# CATS-FAT-MCU.net
KiCad netlist of a schematic drawn in Altium Designer
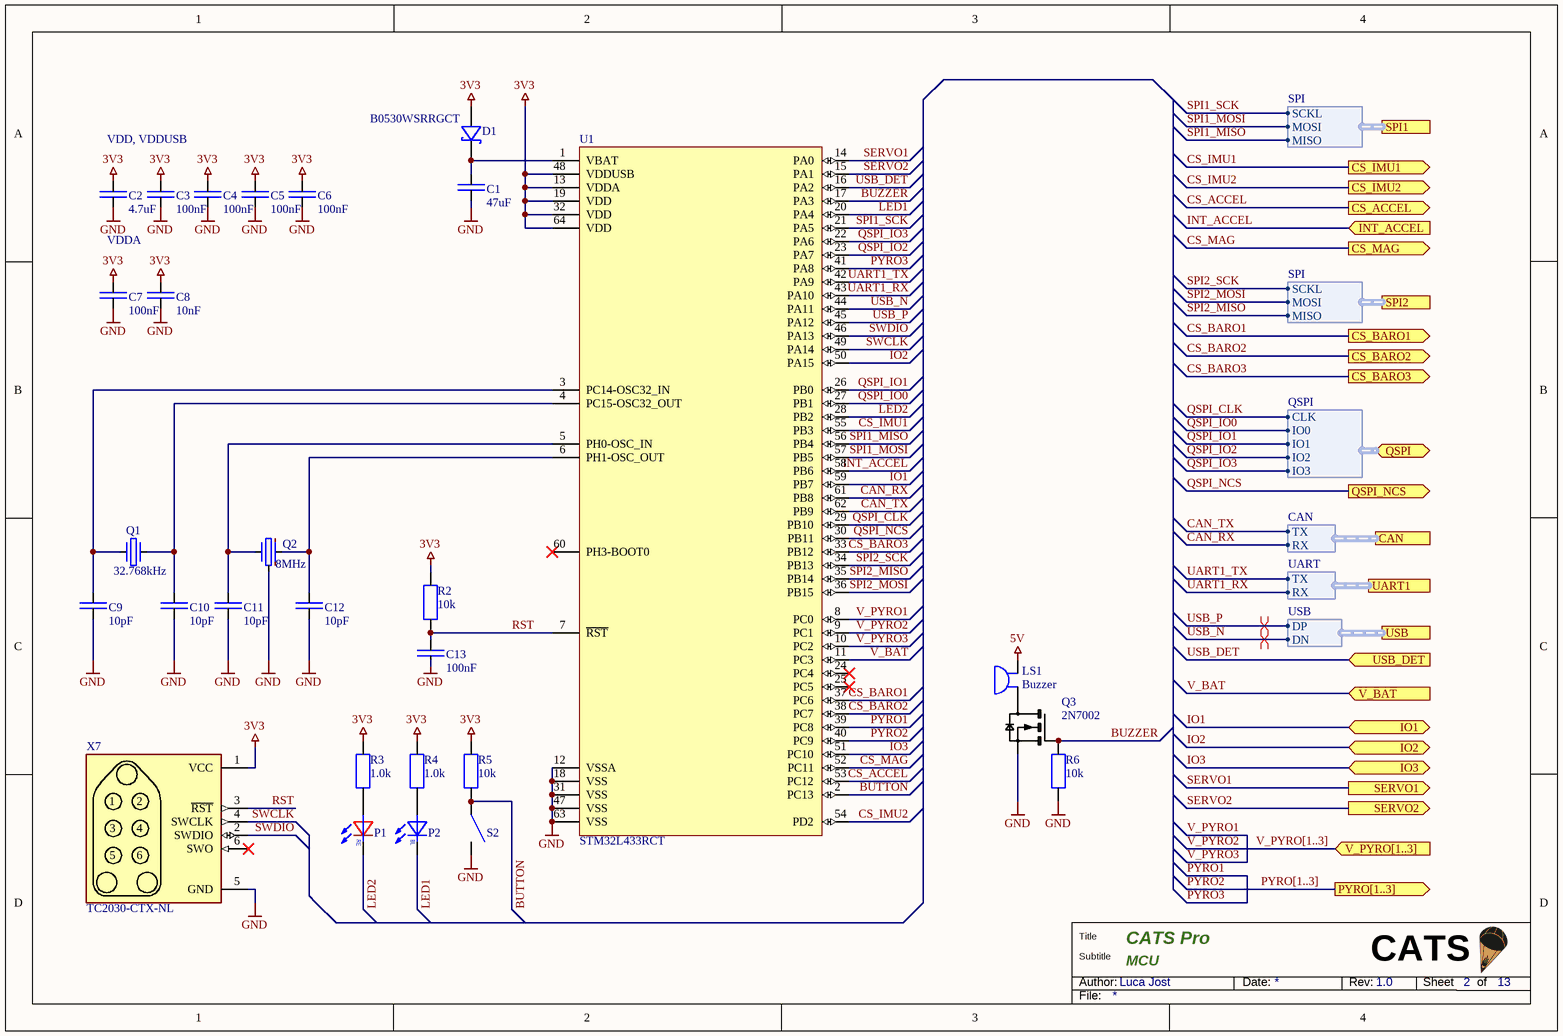
[diagram p0: CATS-FAT-MCU.SchDoc]

(export (version "E")
  (design (tool "Eeschema 10.0.6"))
  (components
    (comp (ref "C1")
      (value "47uF")
      (footprint "SMD Keramikkondensator 0805")
      (description "SMD Ceramic Capacitor E6")
      (libsource (lib "Ceramic Capacitors-E6") (part "E6 - 47uF"))
    )
    (comp (ref "C2")
      (value "4.7uF")
      (footprint "SMD Keramikkondensator 0603")
      (description "SMD Ceramic Capacitor E6")
      (libsource (lib "Ceramic Capacitors-E6") (part "E6 - 4.7uF"))
    )
    (comp (ref "C3")
      (value "100nF")
      (footprint "SMD Keramikkondensator 0603")
      (description "SMD Ceramic Capacitor E6")
      (libsource (lib "Ceramic Capacitors-E6") (part "E6 - 100nF"))
    )
    (comp (ref "C4")
      (value "100nF")
      (footprint "SMD Keramikkondensator 0603")
      (description "SMD Ceramic Capacitor E6")
      (libsource (lib "Ceramic Capacitors-E6") (part "E6 - 100nF"))
    )
    (comp (ref "C5")
      (value "100nF")
      (footprint "SMD Keramikkondensator 0603")
      (description "SMD Ceramic Capacitor E6")
      (libsource (lib "Ceramic Capacitors-E6") (part "E6 - 100nF"))
    )
    (comp (ref "C6")
      (value "100nF")
      (footprint "SMD Keramikkondensator 0603")
      (description "SMD Ceramic Capacitor E6")
      (libsource (lib "Ceramic Capacitors-E6") (part "E6 - 100nF"))
    )
    (comp (ref "C7")
      (value "100nF")
      (footprint "SMD Keramikkondensator 0603")
      (description "SMD Ceramic Capacitor E6")
      (libsource (lib "Ceramic Capacitors-E6") (part "E6 - 100nF"))
    )
    (comp (ref "C8")
      (value "10nF")
      (footprint "SMD Keramikkondensator 0603")
      (description "SMD Ceramic Capacitor E6")
      (libsource (lib "Ceramic Capacitors-E6") (part "E6 - 10nF"))
    )
    (comp (ref "C9")
      (value "10pF")
      (footprint "SMD Keramikkondensator 0603")
      (description "SMD Ceramic Capacitor E6")
      (libsource (lib "Ceramic Capacitors-E6") (part "E6 - 10pF"))
    )
    (comp (ref "C10")
      (value "10pF")
      (footprint "SMD Keramikkondensator 0603")
      (description "SMD Ceramic Capacitor E6")
      (libsource (lib "Ceramic Capacitors-E6") (part "E6 - 10pF"))
    )
    (comp (ref "C11")
      (value "10pF")
      (footprint "SMD Keramikkondensator 0603")
      (description "SMD Ceramic Capacitor E6")
      (libsource (lib "Ceramic Capacitors-E6") (part "E6 - 10pF"))
    )
    (comp (ref "C12")
      (value "10pF")
      (footprint "SMD Keramikkondensator 0603")
      (description "SMD Ceramic Capacitor E6")
      (libsource (lib "Ceramic Capacitors-E6") (part "E6 - 10pF"))
    )
    (comp (ref "C13")
      (value "100nF")
      (footprint "SMD Keramikkondensator 0603")
      (description "SMD Ceramic Capacitor E6")
      (libsource (lib "Ceramic Capacitors-E6") (part "E6 - 100nF"))
    )
    (comp (ref "D1")
      (value "B0530WSRRGCT")
      (footprint "SMD Diode SOD-323F")
      (description "200mW, 0.47V Schottky Barrier Diode")
      (libsource (lib "Diodes") (part "B0530WSRRGCT"))
    )
    (comp (ref "LS1")
      (value "Buzzer")
      (footprint "SMD BUZZER CMT-8504")
      (description "Buzzers Indicator, Internally Driven Piezo 12V 10mA 3kHz 100dB @ 12V, 10cm Through Hole PC Pins")
      (libsource (lib "Other") (part "Buzzer"))
    )
    (comp (ref "P1")
      (value "LED")
      (footprint "SMD LED 0603")
      (description "Color LED")
      (libsource (lib "") (part "LED_1"))
    )
    (comp (ref "P2")
      (value "LED")
      (footprint "SMD LED 0603")
      (description "Color LED")
      (libsource (lib "Diodes") (part "LED"))
    )
    (comp (ref "Q1")
      (value "32.768kHz")
      (footprint "SMD Crystal 3.2x1.5x0.9")
      (description "CRYSTAL 32.7680KHZ 9PF SMD")
      (libsource (lib "Other") (part "Crystal 32.768kHz"))
    )
    (comp (ref "Q2")
      (value "8MHz")
      (footprint "SMD Crystal 3.2X2.5X0.8")
      (description "SMD Crystal Resonators 8MHz ±10ppm SMD,3.2x2.5mm")
      (libsource (lib "Other") (part "Crystal"))
    )
    (comp (ref "Q3")
      (value "2N7002")
      (footprint "SMD MOSFET SOT-23")
      (description "MOSFET N-Channel 20V / 115mA")
      (libsource (lib "Electronic Switches") (part "2N7002"))
    )
    (comp (ref "R2")
      (value "10k")
      (footprint "SMD Widerstand 0603")
      (description "SMD Chip Resistor E24")
      (libsource (lib "Resistors-E24") (part "E24 - 10k"))
    )
    (comp (ref "R3")
      (value "1.0k")
      (footprint "SMD Widerstand 0603")
      (description "SMD Chip Resistor E24")
      (libsource (lib "Resistors-E24") (part "E24 - 1.0k"))
    )
    (comp (ref "R4")
      (value "1.0k")
      (footprint "SMD Widerstand 0603")
      (description "SMD Chip Resistor E24")
      (libsource (lib "Resistors-E24") (part "E24 - 1.0k"))
    )
    (comp (ref "R5")
      (value "10k")
      (footprint "SMD Widerstand 0603")
      (description "SMD Chip Resistor E24")
      (libsource (lib "Resistors-E24") (part "E24 - 10k"))
    )
    (comp (ref "R6")
      (value "10k")
      (footprint "SMD Widerstand 0603")
      (description "SMD Chip Resistor E24")
      (libsource (lib "Resistors-E24") (part "E24 - 10k"))
    )
    (comp (ref "S2")
      (value "SMD-Button")
      (footprint "SMD Button 2.5x3x1.2")
      (description "Button SPST")
      (libsource (lib "Switches") (part "Button 3mmx2.5mm"))
    )
    (comp (ref "U1")
      (value "STM32L433RCT")
      (footprint "SMD IC LQFP64-N")
      (description "ARM® Cortex®-M4 series Microcontroller IC 32-Bit 80MHz 256KB (256K x 8) FLASH 64-LQFP (10x10)")
      (libsource (lib "Microcontrollers") (part "STM32L433RCT"))
    )
    (comp (ref "X7")
      (value "TC2030-CTX-NL")
      (footprint "SMD Connector TC2030 w/ holes")
      (description "Tag-Connect for ARM-Cortex (6-Pin)")
      (libsource (lib "Connectors") (part "TC2030-CTX-NL"))
    )
  )
  (nets
    (net (code "6") (name "/BUTTON") (class "Default")
      (node (ref "R5") (pin "1") (pinfunction "1_1") (pintype "passive"))
      (node (ref "S2") (pin "1") (pinfunction "1_1") (pintype "passive"))
      (node (ref "U1") (pin "2") (pinfunction "PC13_2") (pintype "bidirectional"))
    )
    (net (code "7") (name "/BUZZER") (class "Default")
      (node (ref "Q3") (pin "G") (pinfunction "G_G") (pintype "passive"))
      (node (ref "R6") (pin "2") (pinfunction "2_2") (pintype "passive"))
      (node (ref "U1") (pin "17") (pinfunction "PA3_17") (pintype "bidirectional"))
    )
    (net (code "8") (name "/CAN_RX") (class "Default")
      (node (ref "U1") (pin "61") (pinfunction "PB8_61") (pintype "bidirectional"))
    )
    (net (code "9") (name "/CAN_TX") (class "Default")
      (node (ref "U1") (pin "62") (pinfunction "PB9_62") (pintype "bidirectional"))
    )
    (net (code "10") (name "/CS_ACCEL") (class "Default")
      (node (ref "U1") (pin "53") (pinfunction "PC12_53") (pintype "bidirectional"))
    )
    (net (code "11") (name "/CS_BARO1") (class "Default")
      (node (ref "U1") (pin "37") (pinfunction "PC6_37") (pintype "bidirectional"))
    )
    (net (code "12") (name "/CS_BARO2") (class "Default")
      (node (ref "U1") (pin "38") (pinfunction "PC7_38") (pintype "bidirectional"))
    )
    (net (code "13") (name "/CS_BARO3") (class "Default")
      (node (ref "U1") (pin "33") (pinfunction "PB12_33") (pintype "bidirectional"))
    )
    (net (code "14") (name "/CS_IMU1") (class "Default")
      (node (ref "U1") (pin "55") (pinfunction "PB3_55") (pintype "bidirectional"))
    )
    (net (code "15") (name "/CS_IMU2") (class "Default")
      (node (ref "U1") (pin "54") (pinfunction "PD2_54") (pintype "bidirectional"))
    )
    (net (code "16") (name "/CS_MAG") (class "Default")
      (node (ref "U1") (pin "52") (pinfunction "PC11_52") (pintype "bidirectional"))
    )
    (net (code "17") (name "/INT_ACCEL") (class "Default")
      (node (ref "U1") (pin "58") (pinfunction "PB6_58") (pintype "bidirectional"))
    )
    (net (code "18") (name "/IO1") (class "Default")
      (node (ref "U1") (pin "59") (pinfunction "PB7_59") (pintype "bidirectional"))
    )
    (net (code "19") (name "/IO2") (class "Default")
      (node (ref "U1") (pin "50") (pinfunction "PA15_50") (pintype "bidirectional"))
    )
    (net (code "20") (name "/IO3") (class "Default")
      (node (ref "U1") (pin "51") (pinfunction "PC10_51") (pintype "bidirectional"))
    )
    (net (code "21") (name "/LED1") (class "Default")
      (node (ref "P2") (pin "K") (pinfunction "K_K") (pintype "passive"))
      (node (ref "U1") (pin "20") (pinfunction "PA4_20") (pintype "bidirectional"))
    )
    (net (code "22") (name "/LED2") (class "Default")
      (node (ref "P1") (pin "K") (pinfunction "K_K") (pintype "passive"))
      (node (ref "U1") (pin "28") (pinfunction "PB2_28") (pintype "bidirectional"))
    )
    (net (code "23") (name "/PYRO1") (class "Default")
      (node (ref "U1") (pin "39") (pinfunction "PC8_39") (pintype "bidirectional"))
    )
    (net (code "24") (name "/PYRO2") (class "Default")
      (node (ref "U1") (pin "40") (pinfunction "PC9_40") (pintype "bidirectional"))
    )
    (net (code "25") (name "/PYRO3") (class "Default")
      (node (ref "U1") (pin "41") (pinfunction "PA8_41") (pintype "bidirectional"))
    )
    (net (code "27") (name "/QSPI_CLK") (class "Default")
      (node (ref "U1") (pin "29") (pinfunction "PB10_29") (pintype "bidirectional"))
    )
    (net (code "28") (name "/QSPI_IO0") (class "Default")
      (node (ref "U1") (pin "27") (pinfunction "PB1_27") (pintype "bidirectional"))
    )
    (net (code "29") (name "/QSPI_IO1") (class "Default")
      (node (ref "U1") (pin "26") (pinfunction "PB0_26") (pintype "bidirectional"))
    )
    (net (code "30") (name "/QSPI_IO2") (class "Default")
      (node (ref "U1") (pin "23") (pinfunction "PA7_23") (pintype "bidirectional"))
    )
    (net (code "31") (name "/QSPI_IO3") (class "Default")
      (node (ref "U1") (pin "22") (pinfunction "PA6_22") (pintype "bidirectional"))
    )
    (net (code "32") (name "/QSPI_NCS") (class "Default")
      (node (ref "U1") (pin "30") (pinfunction "PB11_30") (pintype "bidirectional"))
    )
    (net (code "33") (name "/RST") (class "Default")
      (node (ref "C13") (pin "2") (pinfunction "2_2") (pintype "passive"))
      (node (ref "R2") (pin "1") (pinfunction "1_1") (pintype "passive"))
      (node (ref "U1") (pin "7") (pinfunction "~{RST}_7") (pintype "passive"))
      (node (ref "X7") (pin "3") (pinfunction "~{RST}_3") (pintype "output"))
    )
    (net (code "34") (name "/SERVO1") (class "Default")
      (node (ref "U1") (pin "14") (pinfunction "PA0_14") (pintype "bidirectional"))
    )
    (net (code "35") (name "/SERVO2") (class "Default")
      (node (ref "U1") (pin "15") (pinfunction "PA1_15") (pintype "bidirectional"))
    )
    (net (code "36") (name "/SPI1_MISO") (class "Default")
      (node (ref "U1") (pin "56") (pinfunction "PB4_56") (pintype "bidirectional"))
    )
    (net (code "37") (name "/SPI1_MOSI") (class "Default")
      (node (ref "U1") (pin "57") (pinfunction "PB5_57") (pintype "bidirectional"))
    )
    (net (code "38") (name "/SPI1_SCK") (class "Default")
      (node (ref "U1") (pin "21") (pinfunction "PA5_21") (pintype "bidirectional"))
    )
    (net (code "39") (name "/SPI2_MISO") (class "Default")
      (node (ref "U1") (pin "35") (pinfunction "PB14_35") (pintype "bidirectional"))
    )
    (net (code "40") (name "/SPI2_MOSI") (class "Default")
      (node (ref "U1") (pin "36") (pinfunction "PB15_36") (pintype "bidirectional"))
    )
    (net (code "41") (name "/SPI2_SCK") (class "Default")
      (node (ref "U1") (pin "34") (pinfunction "PB13_34") (pintype "bidirectional"))
    )
    (net (code "42") (name "/SWCLK") (class "Default")
      (node (ref "U1") (pin "49") (pinfunction "PA14_49") (pintype "bidirectional"))
      (node (ref "X7") (pin "4") (pinfunction "SWCLK_4") (pintype "output"))
    )
    (net (code "43") (name "/SWDIO") (class "Default")
      (node (ref "U1") (pin "46") (pinfunction "PA13_46") (pintype "bidirectional"))
      (node (ref "X7") (pin "2") (pinfunction "SWDIO_2") (pintype "bidirectional"))
    )
    (net (code "44") (name "/UART1_RX") (class "Default")
      (node (ref "U1") (pin "43") (pinfunction "PA10_43") (pintype "bidirectional"))
    )
    (net (code "45") (name "/UART1_TX") (class "Default")
      (node (ref "U1") (pin "42") (pinfunction "PA9_42") (pintype "bidirectional"))
    )
    (net (code "46") (name "/USB_DET") (class "Default")
      (node (ref "U1") (pin "16") (pinfunction "PA2_16") (pintype "bidirectional"))
    )
    (net (code "47") (name "/USB_N") (class "Default")
      (node (ref "U1") (pin "44") (pinfunction "PA11_44") (pintype "bidirectional"))
    )
    (net (code "48") (name "/USB_P") (class "Default")
      (node (ref "U1") (pin "45") (pinfunction "PA12_45") (pintype "bidirectional"))
    )
    (net (code "49") (name "/V_BAT") (class "Default")
      (node (ref "U1") (pin "11") (pinfunction "PC3_11") (pintype "bidirectional"))
    )
    (net (code "50") (name "/V_PYRO1") (class "Default")
      (node (ref "U1") (pin "8") (pinfunction "PC0_8") (pintype "bidirectional"))
    )
    (net (code "51") (name "/V_PYRO2") (class "Default")
      (node (ref "U1") (pin "9") (pinfunction "PC1_9") (pintype "bidirectional"))
    )
    (net (code "52") (name "/V_PYRO3") (class "Default")
      (node (ref "U1") (pin "10") (pinfunction "PC2_10") (pintype "bidirectional"))
    )
    (net (code "59") (name "3V3") (class "Default")
      (node (ref "C2") (pin "2") (pinfunction "2_2") (pintype "passive"))
      (node (ref "C3") (pin "2") (pinfunction "2_2") (pintype "passive"))
      (node (ref "C4") (pin "2") (pinfunction "2_2") (pintype "passive"))
      (node (ref "C5") (pin "2") (pinfunction "2_2") (pintype "passive"))
      (node (ref "C6") (pin "2") (pinfunction "2_2") (pintype "passive"))
      (node (ref "C7") (pin "2") (pinfunction "2_2") (pintype "passive"))
      (node (ref "C8") (pin "2") (pinfunction "2_2") (pintype "passive"))
      (node (ref "D1") (pin "A") (pinfunction "A_A") (pintype "passive"))
      (node (ref "R2") (pin "2") (pinfunction "2_2") (pintype "passive"))
      (node (ref "R3") (pin "2") (pinfunction "2_2") (pintype "passive"))
      (node (ref "R4") (pin "2") (pinfunction "2_2") (pintype "passive"))
      (node (ref "R5") (pin "2") (pinfunction "2_2") (pintype "passive"))
      (node (ref "U1") (pin "13") (pinfunction "VDDA_13") (pintype "passive"))
      (node (ref "U1") (pin "19") (pinfunction "VDD_19") (pintype "passive"))
      (node (ref "U1") (pin "32") (pinfunction "VDD_32") (pintype "passive"))
      (node (ref "U1") (pin "48") (pinfunction "VDDUSB_48") (pintype "passive"))
      (node (ref "U1") (pin "64") (pinfunction "VDD_64") (pintype "passive"))
      (node (ref "X7") (pin "1") (pinfunction "VCC_1") (pintype "power_in"))
    )
    (net (code "60") (name "5V") (class "Default")
      (node (ref "LS1") (pin "1") (pinfunction "1_1") (pintype "passive"))
    )
    (net (code "61") (name "GND") (class "Default")
      (node (ref "C1") (pin "1") (pinfunction "1_1") (pintype "passive"))
      (node (ref "C10") (pin "1") (pinfunction "1_1") (pintype "passive"))
      (node (ref "C11") (pin "1") (pinfunction "1_1") (pintype "passive"))
      (node (ref "C12") (pin "1") (pinfunction "1_1") (pintype "passive"))
      (node (ref "C13") (pin "1") (pinfunction "1_1") (pintype "passive"))
      (node (ref "C2") (pin "1") (pinfunction "1_1") (pintype "passive"))
      (node (ref "C3") (pin "1") (pinfunction "1_1") (pintype "passive"))
      (node (ref "C4") (pin "1") (pinfunction "1_1") (pintype "passive"))
      (node (ref "C5") (pin "1") (pinfunction "1_1") (pintype "passive"))
      (node (ref "C6") (pin "1") (pinfunction "1_1") (pintype "passive"))
      (node (ref "C7") (pin "1") (pinfunction "1_1") (pintype "passive"))
      (node (ref "C8") (pin "1") (pinfunction "1_1") (pintype "passive"))
      (node (ref "C9") (pin "1") (pinfunction "1_1") (pintype "passive"))
      (node (ref "Q2") (pin "3") (pinfunction "3_3") (pintype "power_in"))
      (node (ref "Q3") (pin "S") (pinfunction "S_S") (pintype "passive"))
      (node (ref "R6") (pin "1") (pinfunction "1_1") (pintype "passive"))
      (node (ref "S2") (pin "2") (pinfunction "2_2") (pintype "passive"))
      (node (ref "U1") (pin "12") (pinfunction "VSSA_12") (pintype "passive"))
      (node (ref "U1") (pin "18") (pinfunction "VSS_18") (pintype "passive"))
      (node (ref "U1") (pin "31") (pinfunction "VSS_31") (pintype "passive"))
      (node (ref "U1") (pin "47") (pinfunction "VSS_47") (pintype "passive"))
      (node (ref "U1") (pin "63") (pinfunction "VSS_63") (pintype "passive"))
      (node (ref "X7") (pin "5") (pinfunction "GND_5") (pintype "power_in"))
    )
    (net (code "62") (name "Net-(LS1-Pad2)") (class "Default")
      (node (ref "LS1") (pin "2") (pinfunction "2_2") (pintype "passive"))
      (node (ref "Q3") (pin "D") (pinfunction "D_D") (pintype "passive"))
    )
    (net (code "63") (name "Net-(P1-PadA)") (class "Default")
      (node (ref "P1") (pin "A") (pinfunction "A_A") (pintype "passive"))
      (node (ref "R3") (pin "1") (pinfunction "1_1") (pintype "passive"))
    )
    (net (code "64") (name "Net-(P2-PadA)") (class "Default")
      (node (ref "P2") (pin "A") (pinfunction "A_A") (pintype "passive"))
      (node (ref "R4") (pin "1") (pinfunction "1_1") (pintype "passive"))
    )
    (net (code "65") (name "Net-(U1-PC14-OSC32_IN)") (class "Default")
      (node (ref "C9") (pin "2") (pinfunction "2_2") (pintype "passive"))
      (node (ref "Q1") (pin "1") (pinfunction "1_1") (pintype "passive"))
      (node (ref "U1") (pin "3") (pinfunction "PC14-OSC32_IN_3") (pintype "passive"))
    )
    (net (code "66") (name "Net-(U1-PC15-OSC32_OUT)") (class "Default")
      (node (ref "C10") (pin "2") (pinfunction "2_2") (pintype "passive"))
      (node (ref "Q1") (pin "2") (pinfunction "2_2") (pintype "passive"))
      (node (ref "U1") (pin "4") (pinfunction "PC15-OSC32_OUT_4") (pintype "passive"))
    )
    (net (code "67") (name "Net-(U1-PH0-OSC_IN)") (class "Default")
      (node (ref "C11") (pin "2") (pinfunction "2_2") (pintype "passive"))
      (node (ref "Q2") (pin "1") (pinfunction "1_1") (pintype "passive"))
      (node (ref "U1") (pin "5") (pinfunction "PH0-OSC_IN_5") (pintype "passive"))
    )
    (net (code "68") (name "Net-(U1-PH1-OSC_OUT)") (class "Default")
      (node (ref "C12") (pin "2") (pinfunction "2_2") (pintype "passive"))
      (node (ref "Q2") (pin "2") (pinfunction "2_2") (pintype "passive"))
      (node (ref "U1") (pin "6") (pinfunction "PH1-OSC_OUT_6") (pintype "passive"))
    )
    (net (code "69") (name "Net-(U1-VBAT)") (class "Default")
      (node (ref "C1") (pin "2") (pinfunction "2_2") (pintype "passive"))
      (node (ref "D1") (pin "K") (pinfunction "K_K") (pintype "passive"))
      (node (ref "U1") (pin "1") (pinfunction "VBAT_1") (pintype "passive"))
    )
    (net (code "70") (name "unconnected-(U1-PC4-Pad24)") (class "Default")
      (node (ref "U1") (pin "24") (pinfunction "PC4_24") (pintype "bidirectional+no_connect"))
    )
    (net (code "71") (name "unconnected-(U1-PC5-Pad25)") (class "Default")
      (node (ref "U1") (pin "25") (pinfunction "PC5_25") (pintype "bidirectional+no_connect"))
    )
    (net (code "72") (name "unconnected-(U1-PH3-BOOT0-Pad60)") (class "Default")
      (node (ref "U1") (pin "60") (pinfunction "PH3-BOOT0_60") (pintype "passive+no_connect"))
    )
    (net (code "73") (name "unconnected-(X7-SWO-Pad6)") (class "Default")
      (node (ref "X7") (pin "6") (pinfunction "SWO_6") (pintype "input+no_connect"))
    )
  )
)
